# Adafruit_QT_Py_ESP32-C3.net
KiCad netlist of a schematic drawn in EAGLE
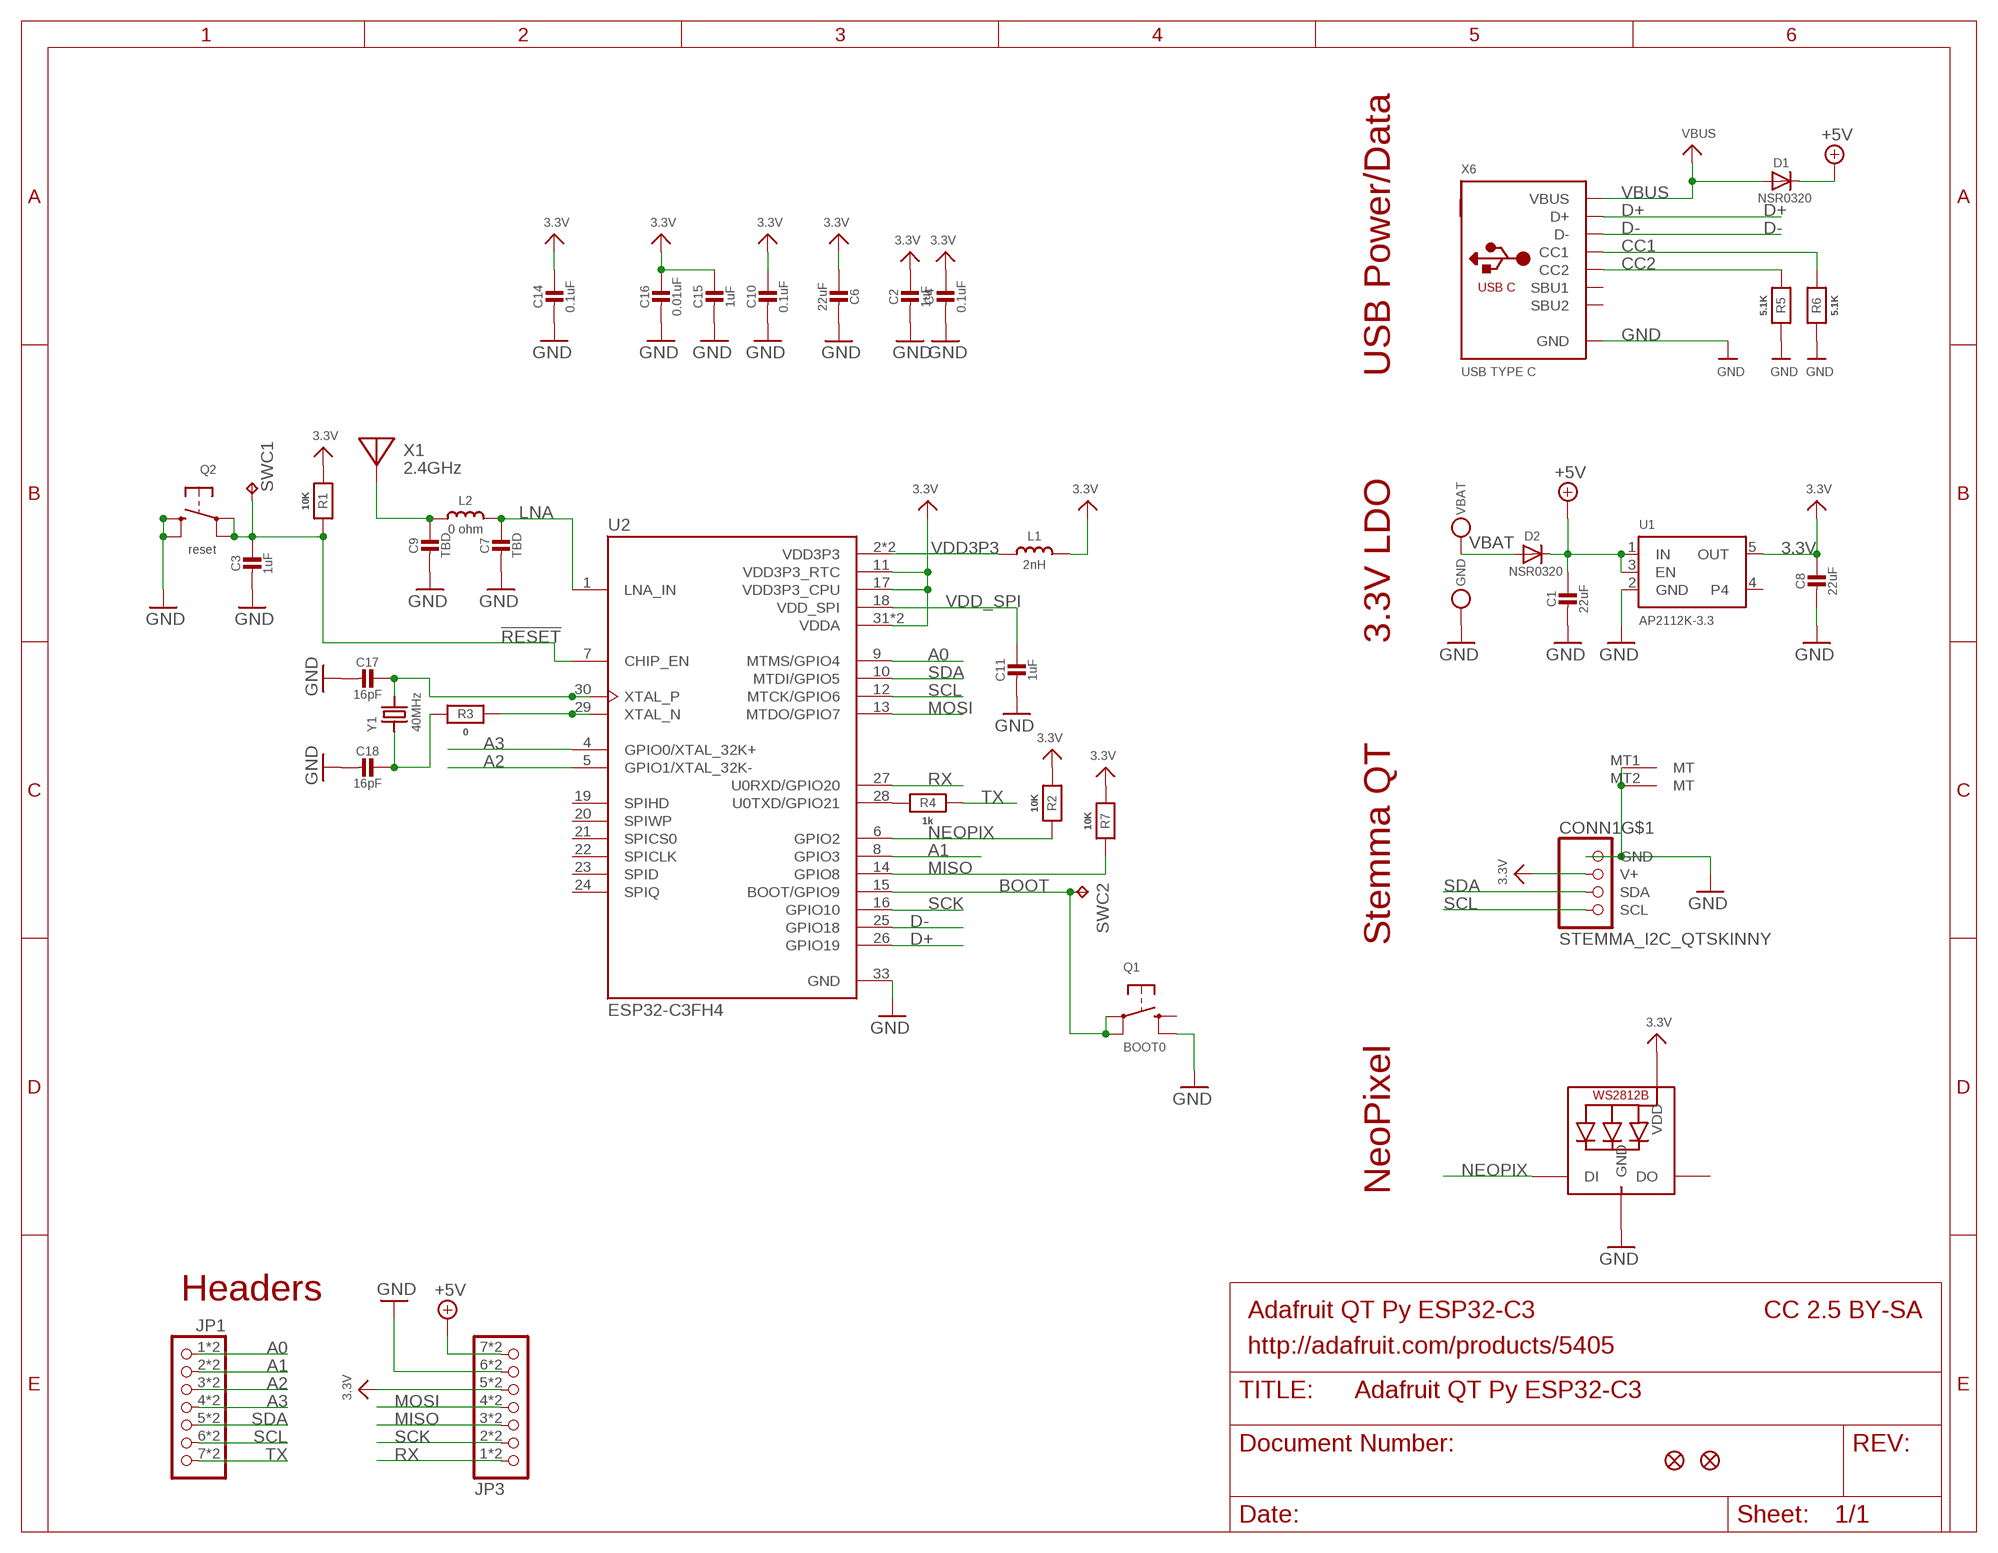
[diagram p0: schematic, sheet 1]

(export (version "E")
  (design (tool "Eeschema 10.0.6"))
  (components
    (comp (ref "C1")
      (value "22uF")
      (footprint "eagle-import:0805-NO")
      (libsource (lib "eagle-import") (part "CAP_CERAMIC0805-NOOUTLINE"))
    )
    (comp (ref "C2")
      (value "1uF")
      (footprint "eagle-import:_0402NO")
      (libsource (lib "eagle-import") (part "CAP_CERAMIC_0402NO"))
    )
    (comp (ref "C3")
      (value "1uF")
      (footprint "eagle-import:_0402NO")
      (libsource (lib "eagle-import") (part "CAP_CERAMIC_0402NO"))
    )
    (comp (ref "C4")
      (value "0.1uF")
      (footprint "eagle-import:_0402NO")
      (libsource (lib "eagle-import") (part "CAP_CERAMIC_0402NO"))
    )
    (comp (ref "C6")
      (value "22uF")
      (footprint "eagle-import:0805-NO")
      (libsource (lib "eagle-import") (part "CAP_CERAMIC0805-NOOUTLINE"))
    )
    (comp (ref "C7")
      (value "TBD")
      (footprint "eagle-import:_0402NO")
      (libsource (lib "eagle-import") (part "CAP_CERAMIC_0402NO"))
    )
    (comp (ref "C8")
      (value "22uF")
      (footprint "eagle-import:0805-NO")
      (libsource (lib "eagle-import") (part "CAP_CERAMIC0805-NOOUTLINE"))
    )
    (comp (ref "C9")
      (value "TBD")
      (footprint "eagle-import:_0402NO")
      (libsource (lib "eagle-import") (part "CAP_CERAMIC_0402NO"))
    )
    (comp (ref "C10")
      (value "0.1uF")
      (footprint "eagle-import:_0402NO")
      (libsource (lib "eagle-import") (part "CAP_CERAMIC_0402NO"))
    )
    (comp (ref "C11")
      (value "1uF")
      (footprint "eagle-import:_0402NO")
      (libsource (lib "eagle-import") (part "CAP_CERAMIC_0402NO"))
    )
    (comp (ref "C14")
      (value "0.1uF")
      (footprint "eagle-import:_0402NO")
      (libsource (lib "eagle-import") (part "CAP_CERAMIC_0402NO"))
    )
    (comp (ref "C15")
      (value "1uF")
      (footprint "eagle-import:_0402NO")
      (libsource (lib "eagle-import") (part "CAP_CERAMIC_0402NO"))
    )
    (comp (ref "C16")
      (value "0.01uF")
      (footprint "eagle-import:_0402NO")
      (libsource (lib "eagle-import") (part "CAP_CERAMIC_0402NO"))
    )
    (comp (ref "C17")
      (value "16pF")
      (footprint "eagle-import:_0402NO")
      (libsource (lib "eagle-import") (part "CAP_CERAMIC_0402NO"))
    )
    (comp (ref "C18")
      (value "16pF")
      (footprint "eagle-import:_0402NO")
      (libsource (lib "eagle-import") (part "CAP_CERAMIC_0402NO"))
    )
    (comp (ref "CONN1")
      (value "STEMMA_I2C_QTSKINNY")
      (footprint "eagle-import:JST_SH4_SKINNY")
      (libsource (lib "eagle-import") (part "STEMMA_I2C_QTSKINNY"))
    )
    (comp (ref "D1")
      (value "NSR0320")
      (footprint "eagle-import:SOD-323_MINI")
      (libsource (lib "eagle-import") (part "DIODE_SOD323MINI"))
    )
    (comp (ref "D2")
      (value "NSR0320")
      (footprint "eagle-import:SOD-323_MINI")
      (libsource (lib "eagle-import") (part "DIODE_SOD323MINI"))
    )
    (comp (ref "GND")
      (value "TESTPOINT_MINUS")
      (footprint "eagle-import:TESTPOINT_MINUS_1X3MM")
      (libsource (lib "eagle-import") (part "TESTPOINT_MINUS"))
    )
    (comp (ref "JP1")
      (value "HEADER-1X7_CASTEL")
      (footprint "eagle-import:1X07_CASTEL")
      (libsource (lib "eagle-import") (part "HEADER-1X7_CASTEL"))
    )
    (comp (ref "JP3")
      (value "HEADER-1X7_CASTEL")
      (footprint "eagle-import:1X07_CASTEL")
      (libsource (lib "eagle-import") (part "HEADER-1X7_CASTEL"))
    )
    (comp (ref "L1")
      (value "2nH")
      (footprint "eagle-import:_0402")
      (libsource (lib "eagle-import") (part "INDUCTOR_0402"))
    )
    (comp (ref "L2")
      (value "0 ohm")
      (footprint "eagle-import:_0402")
      (libsource (lib "eagle-import") (part "INDUCTOR_0402"))
    )
    (comp (ref "LED1")
      (value "WS2812B_SK6805_1515")
      (footprint "eagle-import:SK6805_1515")
      (libsource (lib "eagle-import") (part "WS2812B_SK6805_1515"))
    )
    (comp (ref "Q1")
      (value "BOOT0")
      (footprint "eagle-import:BTN_KMR2_4.6X2.8")
      (libsource (lib "eagle-import") (part "SWITCH_TACT_SMT4.6X2.8"))
    )
    (comp (ref "Q2")
      (value "reset")
      (footprint "eagle-import:BTN_KMR2_SLIM")
      (libsource (lib "eagle-import") (part "SWITCH_TACT_SMT_KMR2SLIM"))
    )
    (comp (ref "R1")
      (value "10K")
      (footprint "eagle-import:_0402NO")
      (libsource (lib "eagle-import") (part "RESISTOR_0402NO"))
    )
    (comp (ref "R2")
      (value "10K")
      (footprint "eagle-import:_0402NO")
      (libsource (lib "eagle-import") (part "RESISTOR_0402NO"))
    )
    (comp (ref "R3")
      (value "0")
      (footprint "eagle-import:_0402NO")
      (libsource (lib "eagle-import") (part "RESISTOR_0402NO"))
    )
    (comp (ref "R4")
      (value "1k")
      (footprint "eagle-import:_0402NO")
      (libsource (lib "eagle-import") (part "RESISTOR_0402NO"))
    )
    (comp (ref "R5")
      (value "5.1K")
      (footprint "eagle-import:_0402NO")
      (libsource (lib "eagle-import") (part "RESISTOR_0402NO"))
    )
    (comp (ref "R6")
      (value "5.1K")
      (footprint "eagle-import:_0402NO")
      (libsource (lib "eagle-import") (part "RESISTOR_0402NO"))
    )
    (comp (ref "R7")
      (value "10K")
      (footprint "eagle-import:_0603MP_TWO6MIL")
      (libsource (lib "eagle-import") (part "RESISTOR_TWO6MIL"))
    )
    (comp (ref "SWC1")
      (value "TPB1,27")
      (footprint "eagle-import:B1,27")
      (libsource (lib "eagle-import") (part "TPB1,27"))
    )
    (comp (ref "SWC2")
      (value "TPB1,27")
      (footprint "eagle-import:B1,27")
      (libsource (lib "eagle-import") (part "TPB1,27"))
    )
    (comp (ref "U$6")
      (value "FIDUCIAL_1MM")
      (footprint "eagle-import:FIDUCIAL_1MM")
      (libsource (lib "eagle-import") (part "FIDUCIAL_1MM"))
    )
    (comp (ref "U$8")
      (value "FIDUCIAL_1MM")
      (footprint "eagle-import:FIDUCIAL_1MM")
      (libsource (lib "eagle-import") (part "FIDUCIAL_1MM"))
    )
    (comp (ref "U1")
      (value "AP2112K-3.3")
      (footprint "eagle-import:SOT23-5")
      (libsource (lib "eagle-import") (part "VREG_SOT23-5"))
    )
    (comp (ref "U2")
      (value "ESP32-C3FH4")
      (footprint "eagle-import:QFN32_5MM")
      (fields
        (field (name "DIGI-KEY_PART_NUMBER") "1904-ESP32-C3FH4CT-ND")
        (field (name "MF") "Espressif Systems")
      )
      (libsource (lib "eagle-import") (part "ESP32-C3FH4"))
    )
    (comp (ref "VBAT")
      (value "TESTPOINT_PLUS13")
      (footprint "eagle-import:TESTPOINT_PLUS_1X3MM")
      (libsource (lib "eagle-import") (part "TESTPOINT_PLUS13"))
    )
    (comp (ref "X1")
      (value "2.4GHz")
      (footprint "eagle-import:ANT_2450AT18B100")
      (libsource (lib "eagle-import") (part "ANTENNA_JOHANSON_2450AT18B100"))
    )
    (comp (ref "X6")
      (value "USB TYPE C")
      (footprint "eagle-import:USB_C_CUSB31-CFM2AX-01-X")
      (libsource (lib "eagle-import") (part "USB_C"))
    )
    (comp (ref "Y1")
      (value "40MHz")
      (footprint "eagle-import:CRYSTAL_2X1.6")
      (libsource (lib "eagle-import") (part "CRYSTAL_2X1.6MM"))
    )
  )
  (nets
    (net (code "1") (name "+5V") (class "Default")
      (node (ref "C1") (pin "1") (pinfunction "1_1") (pintype "passive"))
      (node (ref "D1") (pin "C") (pinfunction "C_C") (pintype "passive"))
      (node (ref "D2") (pin "C") (pinfunction "C_C") (pintype "passive"))
      (node (ref "JP3") (pin "7") (pinfunction "7_7") (pintype "passive"))
      (node (ref "JP3") (pin "7C") (pinfunction "7_7C") (pintype "passive"))
      (node (ref "U1") (pin "1") (pinfunction "IN_1") (pintype "power_in"))
      (node (ref "U1") (pin "3") (pinfunction "EN_3") (pintype "input"))
    )
    (net (code "2") (name "/A0") (class "Default")
      (node (ref "JP1") (pin "1") (pinfunction "1_1") (pintype "passive"))
      (node (ref "JP1") (pin "1C") (pinfunction "1_1C") (pintype "passive"))
      (node (ref "U2") (pin "9") (pinfunction "MTMS/GPIO4_9") (pintype "bidirectional"))
    )
    (net (code "3") (name "/A1") (class "Default")
      (node (ref "JP1") (pin "2") (pinfunction "2_2") (pintype "passive"))
      (node (ref "JP1") (pin "2C") (pinfunction "2_2C") (pintype "passive"))
      (node (ref "U2") (pin "8") (pinfunction "GPIO3_8") (pintype "bidirectional"))
    )
    (net (code "4") (name "/A2") (class "Default")
      (node (ref "JP1") (pin "3") (pinfunction "3_3") (pintype "passive"))
      (node (ref "JP1") (pin "3C") (pinfunction "3_3C") (pintype "passive"))
      (node (ref "U2") (pin "5") (pinfunction "GPIO1/XTAL_32K-_5") (pintype "bidirectional"))
    )
    (net (code "5") (name "/A3") (class "Default")
      (node (ref "JP1") (pin "4") (pinfunction "4_4") (pintype "passive"))
      (node (ref "JP1") (pin "4C") (pinfunction "4_4C") (pintype "passive"))
      (node (ref "U2") (pin "4") (pinfunction "GPIO0/XTAL_32K+_4") (pintype "bidirectional"))
    )
    (net (code "6") (name "/BOOT") (class "Default")
      (node (ref "Q1") (pin "A") (pinfunction "P_A") (pintype "passive"))
      (node (ref "Q1") (pin "A'") (pinfunction "P1_A'") (pintype "passive"))
      (node (ref "SWC2") (pin "TP") (pinfunction "TP_TP") (pintype "input"))
      (node (ref "U2") (pin "15") (pinfunction "BOOT/GPIO9_15") (pintype "bidirectional"))
    )
    (net (code "7") (name "/CC1") (class "Default")
      (node (ref "R6") (pin "2") (pinfunction "2_2") (pintype "passive"))
      (node (ref "X6") (pin "A5") (pinfunction "CC1_A5") (pintype "bidirectional"))
    )
    (net (code "8") (name "/CC2") (class "Default")
      (node (ref "R5") (pin "2") (pinfunction "2_2") (pintype "passive"))
      (node (ref "X6") (pin "B5") (pinfunction "CC2_B5") (pintype "bidirectional"))
    )
    (net (code "9") (name "/D+") (class "Default")
      (node (ref "U2") (pin "26") (pinfunction "GPIO19_26") (pintype "bidirectional"))
      (node (ref "X6") (pin "A6") (pinfunction "D+_A6") (pintype "bidirectional"))
      (node (ref "X6") (pin "B6") (pinfunction "D+_B6") (pintype "bidirectional"))
    )
    (net (code "10") (name "/D-") (class "Default")
      (node (ref "U2") (pin "25") (pinfunction "GPIO18_25") (pintype "bidirectional"))
      (node (ref "X6") (pin "A7") (pinfunction "D-_A7") (pintype "bidirectional"))
      (node (ref "X6") (pin "B7") (pinfunction "D-_B7") (pintype "bidirectional"))
    )
    (net (code "11") (name "/LNA") (class "Default")
      (node (ref "C7") (pin "1") (pinfunction "1_1") (pintype "passive"))
      (node (ref "L2") (pin "2") (pinfunction "2_2") (pintype "passive"))
      (node (ref "U2") (pin "1") (pinfunction "LNA_IN_1") (pintype "bidirectional"))
    )
    (net (code "12") (name "/MISO") (class "Default")
      (node (ref "JP3") (pin "3") (pinfunction "3_3") (pintype "passive"))
      (node (ref "JP3") (pin "3C") (pinfunction "3_3C") (pintype "passive"))
      (node (ref "R7") (pin "2") (pinfunction "2_2") (pintype "passive"))
      (node (ref "U2") (pin "14") (pinfunction "GPIO8_14") (pintype "bidirectional"))
    )
    (net (code "13") (name "/MOSI") (class "Default")
      (node (ref "JP3") (pin "4") (pinfunction "4_4") (pintype "passive"))
      (node (ref "JP3") (pin "4C") (pinfunction "4_4C") (pintype "passive"))
      (node (ref "U2") (pin "13") (pinfunction "MTDO/GPIO7_13") (pintype "bidirectional"))
    )
    (net (code "14") (name "/NEOPIX") (class "Default")
      (node (ref "LED1") (pin "1") (pinfunction "DI_1") (pintype "input"))
      (node (ref "R2") (pin "2") (pinfunction "2_2") (pintype "passive"))
      (node (ref "U2") (pin "6") (pinfunction "GPIO2_6") (pintype "bidirectional"))
    )
    (net (code "15") (name "/RX") (class "Default")
      (node (ref "JP3") (pin "1") (pinfunction "1_1") (pintype "passive"))
      (node (ref "JP3") (pin "1C") (pinfunction "1_1C") (pintype "passive"))
      (node (ref "U2") (pin "27") (pinfunction "U0RXD/GPIO20_27") (pintype "bidirectional"))
    )
    (net (code "16") (name "/SCK") (class "Default")
      (node (ref "JP3") (pin "2") (pinfunction "2_2") (pintype "passive"))
      (node (ref "JP3") (pin "2C") (pinfunction "2_2C") (pintype "passive"))
      (node (ref "U2") (pin "16") (pinfunction "GPIO10_16") (pintype "bidirectional"))
    )
    (net (code "17") (name "/SCL") (class "Default")
      (node (ref "CONN1") (pin "4") (pinfunction "SCL_4") (pintype "passive"))
      (node (ref "JP1") (pin "6") (pinfunction "6_6") (pintype "passive"))
      (node (ref "JP1") (pin "6C") (pinfunction "6_6C") (pintype "passive"))
      (node (ref "U2") (pin "12") (pinfunction "MTCK/GPIO6_12") (pintype "bidirectional"))
    )
    (net (code "18") (name "/SDA") (class "Default")
      (node (ref "CONN1") (pin "3") (pinfunction "SDA_3") (pintype "passive"))
      (node (ref "JP1") (pin "5") (pinfunction "5_5") (pintype "passive"))
      (node (ref "JP1") (pin "5C") (pinfunction "5_5C") (pintype "passive"))
      (node (ref "U2") (pin "10") (pinfunction "MTDI/GPIO5_10") (pintype "bidirectional"))
    )
    (net (code "19") (name "/TX") (class "Default")
      (node (ref "JP1") (pin "7") (pinfunction "7_7") (pintype "passive"))
      (node (ref "JP1") (pin "7C") (pinfunction "7_7C") (pintype "passive"))
      (node (ref "R4") (pin "2") (pinfunction "2_2") (pintype "passive"))
    )
    (net (code "20") (name "/VBAT") (class "Default")
      (node (ref "D2") (pin "A") (pinfunction "A_A") (pintype "passive"))
      (node (ref "VBAT") (pin "P$1") (pinfunction "P$1_P$1") (pintype "bidirectional"))
    )
    (net (code "21") (name "/VDD3P3") (class "Default")
      (node (ref "L1") (pin "2") (pinfunction "2_2") (pintype "passive"))
      (node (ref "U2") (pin "2") (pinfunction "VDD3P3_2") (pintype "power_in"))
      (node (ref "U2") (pin "3") (pinfunction "VDD3P3_3") (pintype "power_in"))
    )
    (net (code "22") (name "/VDD_SPI") (class "Default")
      (node (ref "C11") (pin "1") (pinfunction "1_1") (pintype "passive"))
      (node (ref "U2") (pin "18") (pinfunction "VDD_SPI_18") (pintype "power_in"))
    )
    (net (code "23") (name "/~{RESET}") (class "Default")
      (node (ref "C3") (pin "1") (pinfunction "1_1") (pintype "passive"))
      (node (ref "Q2") (pin "A") (pinfunction "P_A") (pintype "passive"))
      (node (ref "Q2") (pin "A'") (pinfunction "P1_A'") (pintype "passive"))
      (node (ref "R1") (pin "2") (pinfunction "2_2") (pintype "passive"))
      (node (ref "SWC1") (pin "TP") (pinfunction "TP_TP") (pintype "input"))
      (node (ref "U2") (pin "7") (pinfunction "CHIP_EN_7") (pintype "input"))
    )
    (net (code "24") (name "3.3V") (class "Default")
      (node (ref "C10") (pin "1") (pinfunction "1_1") (pintype "passive"))
      (node (ref "C14") (pin "1") (pinfunction "1_1") (pintype "passive"))
      (node (ref "C15") (pin "1") (pinfunction "1_1") (pintype "passive"))
      (node (ref "C16") (pin "1") (pinfunction "1_1") (pintype "passive"))
      (node (ref "C2") (pin "1") (pinfunction "1_1") (pintype "passive"))
      (node (ref "C4") (pin "1") (pinfunction "1_1") (pintype "passive"))
      (node (ref "C6") (pin "1") (pinfunction "1_1") (pintype "passive"))
      (node (ref "C8") (pin "1") (pinfunction "1_1") (pintype "passive"))
      (node (ref "CONN1") (pin "2") (pinfunction "V+_2") (pintype "passive"))
      (node (ref "JP3") (pin "5") (pinfunction "5_5") (pintype "passive"))
      (node (ref "JP3") (pin "5C") (pinfunction "5_5C") (pintype "passive"))
      (node (ref "L1") (pin "1") (pinfunction "1_1") (pintype "passive"))
      (node (ref "LED1") (pin "2") (pinfunction "VDD_2") (pintype "power_in"))
      (node (ref "R1") (pin "1") (pinfunction "1_1") (pintype "passive"))
      (node (ref "R2") (pin "1") (pinfunction "1_1") (pintype "passive"))
      (node (ref "R7") (pin "1") (pinfunction "1_1") (pintype "passive"))
      (node (ref "U1") (pin "5") (pinfunction "OUT_5") (pintype "power_in"))
      (node (ref "U2") (pin "11") (pinfunction "VDD3P3_RTC_11") (pintype "power_in"))
      (node (ref "U2") (pin "17") (pinfunction "VDD3P3_CPU_17") (pintype "power_in"))
      (node (ref "U2") (pin "31") (pinfunction "VDDA_31") (pintype "power_in"))
      (node (ref "U2") (pin "32") (pinfunction "VDDA_32") (pintype "power_in"))
    )
    (net (code "25") (name "GND") (class "Default")
      (node (ref "C1") (pin "2") (pinfunction "2_2") (pintype "passive"))
      (node (ref "C10") (pin "2") (pinfunction "2_2") (pintype "passive"))
      (node (ref "C11") (pin "2") (pinfunction "2_2") (pintype "passive"))
      (node (ref "C14") (pin "2") (pinfunction "2_2") (pintype "passive"))
      (node (ref "C15") (pin "2") (pinfunction "2_2") (pintype "passive"))
      (node (ref "C16") (pin "2") (pinfunction "2_2") (pintype "passive"))
      (node (ref "C17") (pin "2") (pinfunction "2_2") (pintype "passive"))
      (node (ref "C18") (pin "2") (pinfunction "2_2") (pintype "passive"))
      (node (ref "C2") (pin "2") (pinfunction "2_2") (pintype "passive"))
      (node (ref "C3") (pin "2") (pinfunction "2_2") (pintype "passive"))
      (node (ref "C4") (pin "2") (pinfunction "2_2") (pintype "passive"))
      (node (ref "C6") (pin "2") (pinfunction "2_2") (pintype "passive"))
      (node (ref "C7") (pin "2") (pinfunction "2_2") (pintype "passive"))
      (node (ref "C8") (pin "2") (pinfunction "2_2") (pintype "passive"))
      (node (ref "C9") (pin "2") (pinfunction "2_2") (pintype "passive"))
      (node (ref "CONN1") (pin "1") (pinfunction "GND_1") (pintype "passive"))
      (node (ref "CONN1") (pin "MT1") (pinfunction "MT_MT1") (pintype "bidirectional"))
      (node (ref "CONN1") (pin "MT2") (pinfunction "MT_MT2") (pintype "bidirectional"))
      (node (ref "GND") (pin "P$1") (pinfunction "P$1_P$1") (pintype "bidirectional"))
      (node (ref "JP3") (pin "6") (pinfunction "6_6") (pintype "passive"))
      (node (ref "JP3") (pin "6C") (pinfunction "6_6C") (pintype "passive"))
      (node (ref "LED1") (pin "4") (pinfunction "GND_4") (pintype "power_in"))
      (node (ref "Q1") (pin "B'") (pinfunction "S1_B'") (pintype "passive"))
      (node (ref "Q2") (pin "B") (pinfunction "S_B") (pintype "passive"))
      (node (ref "Q2") (pin "B'") (pinfunction "S1_B'") (pintype "passive"))
      (node (ref "R5") (pin "1") (pinfunction "1_1") (pintype "passive"))
      (node (ref "R6") (pin "1") (pinfunction "1_1") (pintype "passive"))
      (node (ref "U1") (pin "2") (pinfunction "GND_2") (pintype "power_in"))
      (node (ref "U2") (pin "33") (pinfunction "GND_33") (pintype "power_in"))
      (node (ref "X6") (pin "A1B12") (pinfunction "GND_A1B12") (pintype "power_in"))
      (node (ref "X6") (pin "B1A12") (pinfunction "GND_B1A12") (pintype "power_in"))
    )
    (net (code "26") (name "Net-(C18-Pad1)") (class "Default")
      (node (ref "C18") (pin "1") (pinfunction "1_1") (pintype "passive"))
      (node (ref "R3") (pin "1") (pinfunction "1_1") (pintype "passive"))
      (node (ref "Y1") (pin "1") (pinfunction "1_1") (pintype "passive"))
    )
    (net (code "27") (name "Net-(U2-U0TXD{slash}GPIO21)") (class "Default")
      (node (ref "R4") (pin "1") (pinfunction "1_1") (pintype "passive"))
      (node (ref "U2") (pin "28") (pinfunction "U0TXD/GPIO21_28") (pintype "bidirectional"))
    )
    (net (code "28") (name "Net-(U2-XTAL_N)") (class "Default")
      (node (ref "R3") (pin "2") (pinfunction "2_2") (pintype "passive"))
      (node (ref "U2") (pin "29") (pinfunction "XTAL_N_29") (pintype "output"))
    )
    (net (code "29") (name "Net-(U2-XTAL_P)") (class "Default")
      (node (ref "C17") (pin "1") (pinfunction "1_1") (pintype "passive"))
      (node (ref "U2") (pin "30") (pinfunction "XTAL_P_30") (pintype "input"))
      (node (ref "Y1") (pin "3") (pinfunction "2_3") (pintype "passive"))
    )
    (net (code "30") (name "Net-(X1-P$1)") (class "Default")
      (node (ref "C9") (pin "1") (pinfunction "1_1") (pintype "passive"))
      (node (ref "L2") (pin "1") (pinfunction "1_1") (pintype "passive"))
      (node (ref "X1") (pin "FP") (pinfunction "P$1_FP") (pintype "passive"))
    )
    (net (code "31") (name "VBUS") (class "Default")
      (node (ref "D1") (pin "A") (pinfunction "A_A") (pintype "passive"))
      (node (ref "X6") (pin "A4B9") (pinfunction "VBUS_A4B9") (pintype "power_in"))
      (node (ref "X6") (pin "B4A9") (pinfunction "VBUS_B4A9") (pintype "power_in"))
    )
    (net (code "32") (name "unconnected-(LED1-DO-Pad3)") (class "Default")
      (node (ref "LED1") (pin "3") (pinfunction "DO_3") (pintype "output"))
    )
    (net (code "33") (name "unconnected-(Q1-S-PadB)") (class "Default")
      (node (ref "Q1") (pin "B") (pinfunction "S_B") (pintype "passive"))
    )
    (net (code "34") (name "unconnected-(U1-P4-Pad4)") (class "Default")
      (node (ref "U1") (pin "4") (pinfunction "P4_4") (pintype "bidirectional"))
    )
    (net (code "35") (name "unconnected-(U2-SPICLK-Pad22)") (class "Default")
      (node (ref "U2") (pin "22") (pinfunction "SPICLK_22") (pintype "no_connect"))
    )
    (net (code "36") (name "unconnected-(U2-SPICS0-Pad21)") (class "Default")
      (node (ref "U2") (pin "21") (pinfunction "SPICS0_21") (pintype "no_connect"))
    )
    (net (code "37") (name "unconnected-(U2-SPID-Pad23)") (class "Default")
      (node (ref "U2") (pin "23") (pinfunction "SPID_23") (pintype "no_connect"))
    )
    (net (code "38") (name "unconnected-(U2-SPIHD-Pad19)") (class "Default")
      (node (ref "U2") (pin "19") (pinfunction "SPIHD_19") (pintype "no_connect"))
    )
    (net (code "39") (name "unconnected-(U2-SPIQ-Pad24)") (class "Default")
      (node (ref "U2") (pin "24") (pinfunction "SPIQ_24") (pintype "no_connect"))
    )
    (net (code "40") (name "unconnected-(U2-SPIWP-Pad20)") (class "Default")
      (node (ref "U2") (pin "20") (pinfunction "SPIWP_20") (pintype "no_connect"))
    )
    (net (code "41") (name "unconnected-(X6-SBU1-PadA8)") (class "Default")
      (node (ref "X6") (pin "A8") (pinfunction "SBU1_A8") (pintype "bidirectional"))
    )
    (net (code "42") (name "unconnected-(X6-SBU2-PadB8)") (class "Default")
      (node (ref "X6") (pin "B8") (pinfunction "SBU2_B8") (pintype "bidirectional"))
    )
  )
)
